# Cameras.net
KiCad netlist of a schematic drawn in Altium Designer
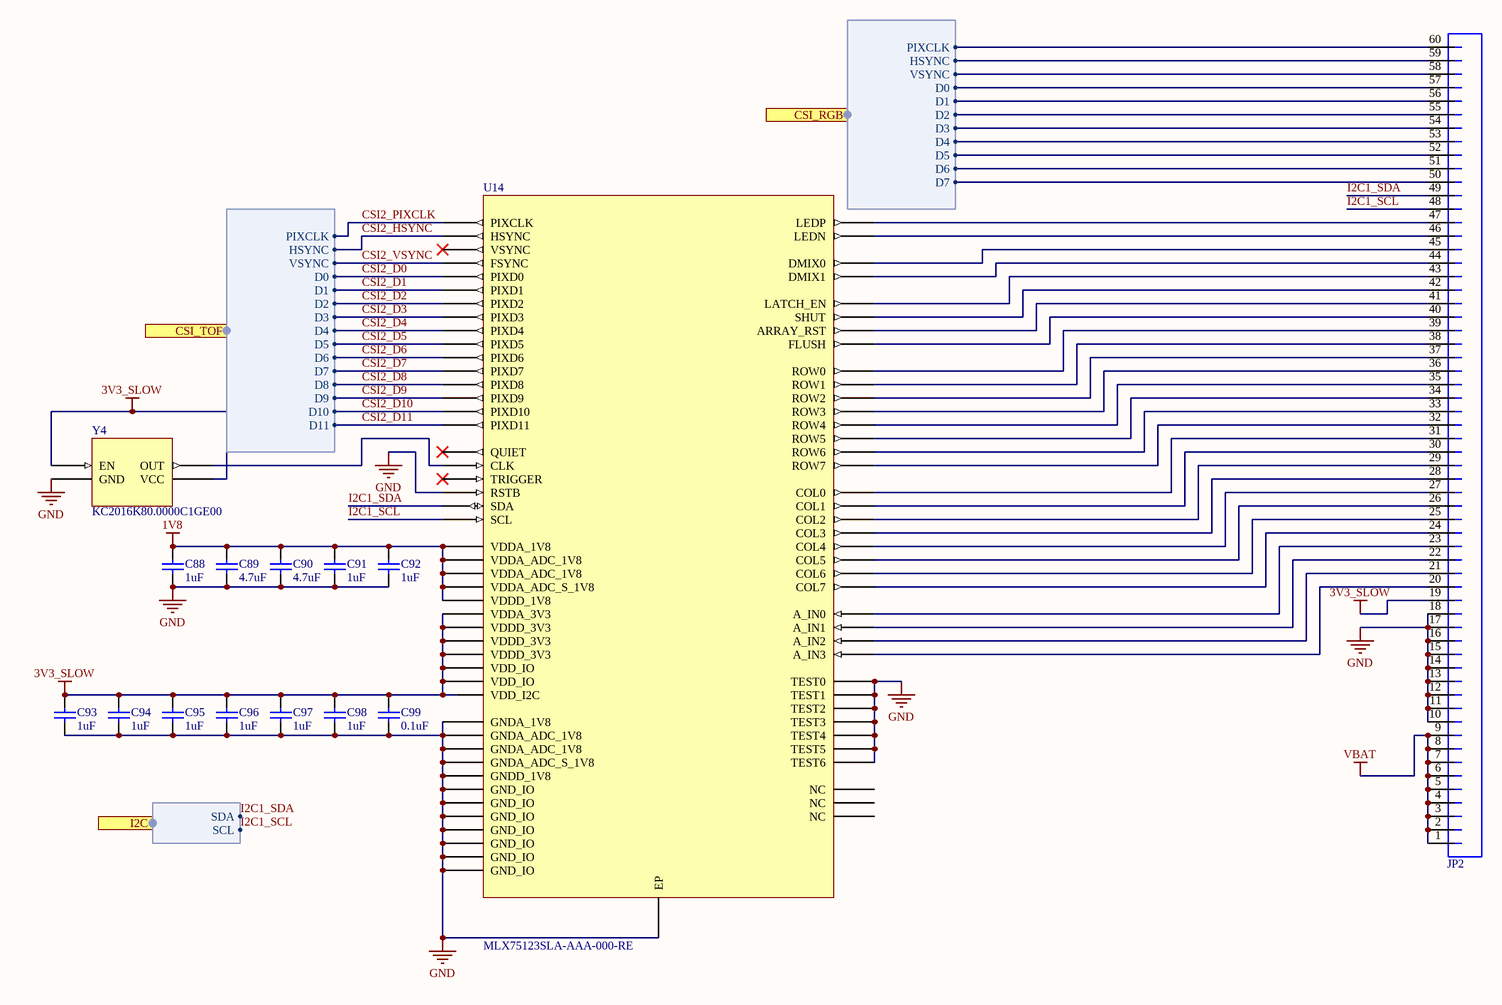
[diagram p0: Cameras.SchDoc]

(export (version "E")
  (design (tool "Eeschema 10.0.6"))
  (components
    (comp (ref "C88")
      (value "1uF")
      (footprint "C0402[1005X55]")
      (description "1uF 6.3V 10% 0402 (1005 Metric)")
      (fields (field (name "PARTNUMBER") "GRM155R70J105KA12D") (field (name "MANUFACTURER") "Murata"))
      (libsource (lib "Capacitors") (part "CAP_1uF_6.3V_0402_10%"))
    )
    (comp (ref "C89")
      (value "4.7uF")
      (footprint "C0402[1005X55]")
      (description "4.7uF 6.3V 20% 0402 (1005 Metric)")
      (fields (field (name "PARTNUMBER") "GRM155R60J475ME47D") (field (name "MANUFACTURER") "Murata"))
      (libsource (lib "Capacitors") (part "CAP_4.7uF_6.3V_0402_20%"))
    )
    (comp (ref "C90")
      (value "4.7uF")
      (footprint "C0402[1005X55]")
      (description "4.7uF 6.3V 20% 0402 (1005 Metric)")
      (fields (field (name "PARTNUMBER") "GRM155R60J475ME47D") (field (name "MANUFACTURER") "Murata"))
      (libsource (lib "Capacitors") (part "CAP_4.7uF_6.3V_0402_20%"))
    )
    (comp (ref "C91")
      (value "1uF")
      (footprint "C0402[1005X55]")
      (description "1uF 6.3V 10% 0402 (1005 Metric)")
      (fields (field (name "PARTNUMBER") "GRM155R70J105KA12D") (field (name "MANUFACTURER") "Murata"))
      (libsource (lib "Capacitors") (part "CAP_1uF_6.3V_0402_10%"))
    )
    (comp (ref "C92")
      (value "1uF")
      (footprint "C0402[1005X55]")
      (description "1uF 6.3V 10% 0402 (1005 Metric)")
      (fields (field (name "PARTNUMBER") "GRM155R70J105KA12D") (field (name "MANUFACTURER") "Murata"))
      (libsource (lib "Capacitors") (part "CAP_1uF_6.3V_0402_10%"))
    )
    (comp (ref "C93")
      (value "1uF")
      (footprint "C0402[1005X55]")
      (description "1uF 6.3V 10% 0402 (1005 Metric)")
      (fields (field (name "PARTNUMBER") "GRM155R70J105KA12D") (field (name "MANUFACTURER") "Murata"))
      (libsource (lib "Capacitors") (part "CAP_1uF_6.3V_0402_10%"))
    )
    (comp (ref "C94")
      (value "1uF")
      (footprint "C0402[1005X55]")
      (description "1uF 6.3V 10% 0402 (1005 Metric)")
      (fields (field (name "PARTNUMBER") "GRM155R70J105KA12D") (field (name "MANUFACTURER") "Murata"))
      (libsource (lib "Capacitors") (part "CAP_1uF_6.3V_0402_10%"))
    )
    (comp (ref "C95")
      (value "1uF")
      (footprint "C0402[1005X55]")
      (description "1uF 6.3V 10% 0402 (1005 Metric)")
      (fields (field (name "PARTNUMBER") "GRM155R70J105KA12D") (field (name "MANUFACTURER") "Murata"))
      (libsource (lib "Capacitors") (part "CAP_1uF_6.3V_0402_10%"))
    )
    (comp (ref "C96")
      (value "1uF")
      (footprint "C0402[1005X55]")
      (description "1uF 6.3V 10% 0402 (1005 Metric)")
      (fields (field (name "PARTNUMBER") "GRM155R70J105KA12D") (field (name "MANUFACTURER") "Murata"))
      (libsource (lib "Capacitors") (part "CAP_1uF_6.3V_0402_10%"))
    )
    (comp (ref "C97")
      (value "1uF")
      (footprint "C0402[1005X55]")
      (description "1uF 6.3V 10% 0402 (1005 Metric)")
      (fields (field (name "PARTNUMBER") "GRM155R70J105KA12D") (field (name "MANUFACTURER") "Murata"))
      (libsource (lib "Capacitors") (part "CAP_1uF_6.3V_0402_10%"))
    )
    (comp (ref "C98")
      (value "1uF")
      (footprint "C0402[1005X55]")
      (description "1uF 6.3V 10% 0402 (1005 Metric)")
      (fields (field (name "PARTNUMBER") "GRM155R70J105KA12D") (field (name "MANUFACTURER") "Murata"))
      (libsource (lib "Capacitors") (part "CAP_1uF_6.3V_0402_10%"))
    )
    (comp (ref "C99")
      (value "0.1uF")
      (footprint "C0402[1005X55]")
      (description "0.1uF 6.3V 10% 0402 (1005 Metric)")
      (fields (field (name "PARTNUMBER") "GRM155R70J104KA01D") (field (name "MANUFACTURER") "Murata"))
      (libsource (lib "Capacitors") (part "CAP_0.1uF_6.3V_0402_10%"))
    )
    (comp (ref "JP2")
      (value "JST_JMD_60_HORZ")
      (footprint "JST-JMD-60-SMD-HORZ")
      (fields
        (field (name "MANUFACTURER") "JST Sales America, Inc.")
        (field (name "PARTNUMBER") "60PS-JMDSS-G-1-TF")
      )
      (libsource (lib "Connectors") (part "JST_JMD_60_HORZ"))
    )
    (comp (ref "U14")
      (value "MLX75123SLA-AAA-000-RE")
      (footprint "AQFN-84")
      (description "Sensor Interface ToF Companion Chip")
      (fields (field (name "MANUFACTURER") "Melexis"))
      (libsource (lib "ICs") (part "MLX75123SLA-AAA-000-RE"))
    )
    (comp (ref "Y4")
      (value "KC2016K80.0000C1GE00")
      (footprint "KC2016K")
      (description "OSC XO 80.0000MHZ CMOS SMD")
      (fields (field (name "MANUFACTURER") "AVX"))
      (libsource (lib "Components") (part "KC2016K80.0000C1GE00"))
    )
  )
  (nets
    (net (code "4") (name "/CSI2_D0") (class "Default")
      (node (ref "U14") (pin "A30") (pinfunction "PIXD0_A30") (pintype "output"))
    )
    (net (code "5") (name "/CSI2_D1") (class "Default")
      (node (ref "U14") (pin "B27") (pinfunction "PIXD1_B27") (pintype "output"))
    )
    (net (code "6") (name "/CSI2_D2") (class "Default")
      (node (ref "U14") (pin "A29") (pinfunction "PIXD2_A29") (pintype "output"))
    )
    (net (code "7") (name "/CSI2_D3") (class "Default")
      (node (ref "U14") (pin "B26") (pinfunction "PIXD3_B26") (pintype "output"))
    )
    (net (code "8") (name "/CSI2_D4") (class "Default")
      (node (ref "U14") (pin "A28") (pinfunction "PIXD4_A28") (pintype "output"))
    )
    (net (code "9") (name "/CSI2_D5") (class "Default")
      (node (ref "U14") (pin "B25") (pinfunction "PIXD5_B25") (pintype "output"))
    )
    (net (code "10") (name "/CSI2_D6") (class "Default")
      (node (ref "U14") (pin "A27") (pinfunction "PIXD6_A27") (pintype "output"))
    )
    (net (code "11") (name "/CSI2_D7") (class "Default")
      (node (ref "U14") (pin "B24") (pinfunction "PIXD7_B24") (pintype "output"))
    )
    (net (code "12") (name "/CSI2_D8") (class "Default")
      (node (ref "U14") (pin "A26") (pinfunction "PIXD8_A26") (pintype "output"))
    )
    (net (code "13") (name "/CSI2_D9") (class "Default")
      (node (ref "U14") (pin "B23") (pinfunction "PIXD9_B23") (pintype "output"))
    )
    (net (code "14") (name "/CSI2_D10") (class "Default")
      (node (ref "U14") (pin "A25") (pinfunction "PIXD10_A25") (pintype "output"))
    )
    (net (code "15") (name "/CSI2_D11") (class "Default")
      (node (ref "U14") (pin "B22") (pinfunction "PIXD11_B22") (pintype "output"))
    )
    (net (code "16") (name "/CSI2_HSYNC") (class "Default")
      (node (ref "U14") (pin "B29") (pinfunction "HSYNC_B29") (pintype "output"))
    )
    (net (code "17") (name "/CSI2_PIXCLK") (class "Default")
      (node (ref "U14") (pin "B28") (pinfunction "PIXCLK_B28") (pintype "output"))
    )
    (net (code "18") (name "/CSI2_VSYNC") (class "Default")
      (node (ref "U14") (pin "A31") (pinfunction "FSYNC_A31") (pintype "output"))
    )
    (net (code "19") (name "/I2C1_SCL") (class "Default")
      (node (ref "JP2") (pin "48") (pinfunction "48_48") (pintype "passive"))
      (node (ref "U14") (pin "A12") (pinfunction "SCL_A12") (pintype "input"))
    )
    (net (code "20") (name "/I2C1_SDA") (class "Default")
      (node (ref "JP2") (pin "49") (pinfunction "49_49") (pintype "passive"))
      (node (ref "U14") (pin "B11") (pinfunction "SDA_B11") (pintype "bidirectional"))
    )
    (net (code "24") (name "1V8") (class "Default")
      (node (ref "C88") (pin "2") (pinfunction "2_2") (pintype "passive"))
      (node (ref "C89") (pin "2") (pinfunction "2_2") (pintype "passive"))
      (node (ref "C90") (pin "2") (pinfunction "2_2") (pintype "passive"))
      (node (ref "C91") (pin "2") (pinfunction "2_2") (pintype "passive"))
      (node (ref "C92") (pin "2") (pinfunction "2_2") (pintype "passive"))
      (node (ref "U14") (pin "A10") (pinfunction "VDDA_ADC_S_1V8_A10") (pintype "power_in"))
      (node (ref "U14") (pin "A9") (pinfunction "VDDA_ADC_1V8_A9") (pintype "power_in"))
      (node (ref "U14") (pin "B14") (pinfunction "VDDA_1V8_B14") (pintype "power_in"))
      (node (ref "U14") (pin "B20") (pinfunction "VDDD_1V8_B20") (pintype "power_in"))
      (node (ref "U14") (pin "B5") (pinfunction "VDDA_ADC_1V8_B5") (pintype "power_in"))
    )
    (net (code "25") (name "3V3_SLOW") (class "Default")
      (node (ref "C93") (pin "2") (pinfunction "2_2") (pintype "passive"))
      (node (ref "C94") (pin "2") (pinfunction "2_2") (pintype "passive"))
      (node (ref "C95") (pin "2") (pinfunction "2_2") (pintype "passive"))
      (node (ref "C96") (pin "2") (pinfunction "2_2") (pintype "passive"))
      (node (ref "C97") (pin "2") (pinfunction "2_2") (pintype "passive"))
      (node (ref "C98") (pin "2") (pinfunction "2_2") (pintype "passive"))
      (node (ref "C99") (pin "2") (pinfunction "2_2") (pintype "passive"))
      (node (ref "JP2") (pin "19") (pinfunction "19_19") (pintype "passive"))
      (node (ref "U14") (pin "A36") (pinfunction "VDDD_3V3_A36") (pintype "power_in"))
      (node (ref "U14") (pin "B12") (pinfunction "VDD_I2C_B12") (pintype "power_in"))
      (node (ref "U14") (pin "B17") (pinfunction "VDDD_3V3_B17") (pintype "power_in"))
      (node (ref "U14") (pin "B21") (pinfunction "VDD_IO_B21") (pintype "power_in"))
      (node (ref "U14") (pin "B30") (pinfunction "VDD_IO_B30") (pintype "power_in"))
      (node (ref "U14") (pin "B38") (pinfunction "VDDD_3V3_B38") (pintype "power_in"))
      (node (ref "U14") (pin "B4") (pinfunction "VDDA_3V3_B4") (pintype "power_in"))
      (node (ref "Y4") (pin "1") (pinfunction "EN_1") (pintype "input"))
      (node (ref "Y4") (pin "4") (pinfunction "VCC_4") (pintype "power_in"))
    )
    (net (code "26") (name "GND") (class "Default")
      (node (ref "C88") (pin "1") (pinfunction "1_1") (pintype "passive"))
      (node (ref "C89") (pin "1") (pinfunction "1_1") (pintype "passive"))
      (node (ref "C90") (pin "1") (pinfunction "1_1") (pintype "passive"))
      (node (ref "C91") (pin "1") (pinfunction "1_1") (pintype "passive"))
      (node (ref "C92") (pin "1") (pinfunction "1_1") (pintype "passive"))
      (node (ref "C93") (pin "1") (pinfunction "1_1") (pintype "passive"))
      (node (ref "C94") (pin "1") (pinfunction "1_1") (pintype "passive"))
      (node (ref "C95") (pin "1") (pinfunction "1_1") (pintype "passive"))
      (node (ref "C96") (pin "1") (pinfunction "1_1") (pintype "passive"))
      (node (ref "C97") (pin "1") (pinfunction "1_1") (pintype "passive"))
      (node (ref "C98") (pin "1") (pinfunction "1_1") (pintype "passive"))
      (node (ref "C99") (pin "1") (pinfunction "1_1") (pintype "passive"))
      (node (ref "JP2") (pin "10") (pinfunction "10_10") (pintype "passive"))
      (node (ref "JP2") (pin "11") (pinfunction "11_11") (pintype "passive"))
      (node (ref "JP2") (pin "12") (pinfunction "12_12") (pintype "passive"))
      (node (ref "JP2") (pin "13") (pinfunction "13_13") (pintype "passive"))
      (node (ref "JP2") (pin "14") (pinfunction "14_14") (pintype "passive"))
      (node (ref "JP2") (pin "15") (pinfunction "15_15") (pintype "passive"))
      (node (ref "JP2") (pin "16") (pinfunction "16_16") (pintype "passive"))
      (node (ref "JP2") (pin "17") (pinfunction "17_17") (pintype "passive"))
      (node (ref "JP2") (pin "18") (pinfunction "18_18") (pintype "passive"))
      (node (ref "U14") (pin "A11") (pinfunction "TEST5_A11") (pintype "passive"))
      (node (ref "U14") (pin "A14") (pinfunction "RSTB_A14") (pintype "input"))
      (node (ref "U14") (pin "A16") (pinfunction "GNDA_1V8_A16") (pintype "power_in"))
      (node (ref "U14") (pin "A17") (pinfunction "TEST3_A17") (pintype "passive"))
      (node (ref "U14") (pin "A18") (pinfunction "GND_IO_A18") (pintype "power_in"))
      (node (ref "U14") (pin "A21") (pinfunction "TEST0_A21") (pintype "passive"))
      (node (ref "U14") (pin "A22") (pinfunction "GNDD_1V8_A22") (pintype "power_in"))
      (node (ref "U14") (pin "A24") (pinfunction "GND_IO_A24") (pintype "power_in"))
      (node (ref "U14") (pin "A33") (pinfunction "GND_IO_A33") (pintype "power_in"))
      (node (ref "U14") (pin "A41") (pinfunction "GND_IO_A41") (pintype "power_in"))
      (node (ref "U14") (pin "A5") (pinfunction "GNDA_ADC_1V8_A5") (pintype "power_in"))
      (node (ref "U14") (pin "A8") (pinfunction "GND_IO_A8") (pintype "power_in"))
      (node (ref "U14") (pin "B10") (pinfunction "TEST6_B10") (pintype "passive"))
      (node (ref "U14") (pin "B15") (pinfunction "GND_IO_B15") (pintype "power_in"))
      (node (ref "U14") (pin "B16") (pinfunction "TEST4_B16") (pintype "passive"))
      (node (ref "U14") (pin "B18") (pinfunction "TEST2_B18") (pintype "passive"))
      (node (ref "U14") (pin "B19") (pinfunction "TEST1_B19") (pintype "passive"))
      (node (ref "U14") (pin "B33") (pinfunction "GND_IO_B33") (pintype "power_in"))
      (node (ref "U14") (pin "B8") (pinfunction "GNDA_ADC_1V8_B8") (pintype "power_in"))
      (node (ref "U14") (pin "B9") (pinfunction "GNDA_ADC_S_1V8_B9") (pintype "power_in"))
      (node (ref "U14") (pin "EP") (pinfunction "EP_EP") (pintype "passive"))
      (node (ref "Y4") (pin "2") (pinfunction "GND_2") (pintype "power_in"))
    )
    (net (code "27") (name "Net-(U14-ARRAY_RST)") (class "Default")
      (node (ref "JP2") (pin "41") (pinfunction "41_41") (pintype "passive"))
      (node (ref "U14") (pin "A3") (pinfunction "ARRAY_RST_A3") (pintype "output"))
    )
    (net (code "28") (name "Net-(U14-A_IN0)") (class "Default")
      (node (ref "JP2") (pin "23") (pinfunction "23_23") (pintype "passive"))
      (node (ref "U14") (pin "B6") (pinfunction "A_IN0_B6") (pintype "input"))
    )
    (net (code "29") (name "Net-(U14-A_IN1)") (class "Default")
      (node (ref "JP2") (pin "22") (pinfunction "22_22") (pintype "passive"))
      (node (ref "U14") (pin "A6") (pinfunction "A_IN1_A6") (pintype "input"))
    )
    (net (code "30") (name "Net-(U14-A_IN2)") (class "Default")
      (node (ref "JP2") (pin "21") (pinfunction "21_21") (pintype "passive"))
      (node (ref "U14") (pin "A7") (pinfunction "A_IN2_A7") (pintype "input"))
    )
    (net (code "31") (name "Net-(U14-A_IN3)") (class "Default")
      (node (ref "JP2") (pin "20") (pinfunction "20_20") (pintype "passive"))
      (node (ref "U14") (pin "B7") (pinfunction "A_IN3_B7") (pintype "input"))
    )
    (net (code "32") (name "Net-(U14-CLK)") (class "Default")
      (node (ref "U14") (pin "B13") (pinfunction "CLK_B13") (pintype "input"))
      (node (ref "Y4") (pin "3") (pinfunction "OUT_3") (pintype "output"))
    )
    (net (code "33") (name "Net-(U14-COL0)") (class "Default")
      (node (ref "JP2") (pin "31") (pinfunction "31_31") (pintype "passive"))
      (node (ref "U14") (pin "B37") (pinfunction "COL0_B37") (pintype "output"))
    )
    (net (code "34") (name "Net-(U14-COL1)") (class "Default")
      (node (ref "JP2") (pin "30") (pinfunction "30_30") (pintype "passive"))
      (node (ref "U14") (pin "A40") (pinfunction "COL1_A40") (pintype "output"))
    )
    (net (code "35") (name "Net-(U14-COL2)") (class "Default")
      (node (ref "JP2") (pin "29") (pinfunction "29_29") (pintype "passive"))
      (node (ref "U14") (pin "B36") (pinfunction "COL2_B36") (pintype "output"))
    )
    (net (code "36") (name "Net-(U14-COL3)") (class "Default")
      (node (ref "JP2") (pin "28") (pinfunction "28_28") (pintype "passive"))
      (node (ref "U14") (pin "A39") (pinfunction "COL3_A39") (pintype "output"))
    )
    (net (code "37") (name "Net-(U14-COL4)") (class "Default")
      (node (ref "JP2") (pin "27") (pinfunction "27_27") (pintype "passive"))
      (node (ref "U14") (pin "B35") (pinfunction "COL4_B35") (pintype "output"))
    )
    (net (code "38") (name "Net-(U14-COL5)") (class "Default")
      (node (ref "JP2") (pin "26") (pinfunction "26_26") (pintype "passive"))
      (node (ref "U14") (pin "A38") (pinfunction "COL5_A38") (pintype "output"))
    )
    (net (code "39") (name "Net-(U14-COL6)") (class "Default")
      (node (ref "JP2") (pin "25") (pinfunction "25_25") (pintype "passive"))
      (node (ref "U14") (pin "B34") (pinfunction "COL6_B34") (pintype "output"))
    )
    (net (code "40") (name "Net-(U14-COL7)") (class "Default")
      (node (ref "JP2") (pin "24") (pinfunction "24_24") (pintype "passive"))
      (node (ref "U14") (pin "A37") (pinfunction "COL7_A37") (pintype "output"))
    )
    (net (code "41") (name "Net-(U14-DMIX0)") (class "Default")
      (node (ref "JP2") (pin "45") (pinfunction "45_45") (pintype "passive"))
      (node (ref "U14") (pin "A35") (pinfunction "DMIX0_A35") (pintype "output"))
    )
    (net (code "42") (name "Net-(U14-DMIX1)") (class "Default")
      (node (ref "JP2") (pin "44") (pinfunction "44_44") (pintype "passive"))
      (node (ref "U14") (pin "B32") (pinfunction "DMIX1_B32") (pintype "output"))
    )
    (net (code "43") (name "Net-(U14-FLUSH)") (class "Default")
      (node (ref "JP2") (pin "40") (pinfunction "40_40") (pintype "passive"))
      (node (ref "U14") (pin "B3") (pinfunction "FLUSH_B3") (pintype "output"))
    )
    (net (code "44") (name "Net-(U14-LATCH_EN)") (class "Default")
      (node (ref "JP2") (pin "43") (pinfunction "43_43") (pintype "passive"))
      (node (ref "U14") (pin "A4") (pinfunction "LATCH_EN_A4") (pintype "output"))
    )
    (net (code "45") (name "Net-(U14-LEDN)") (class "Default")
      (node (ref "JP2") (pin "46") (pinfunction "46_46") (pintype "passive"))
      (node (ref "U14") (pin "A34") (pinfunction "LEDN_A34") (pintype "output"))
    )
    (net (code "46") (name "Net-(U14-LEDP)") (class "Default")
      (node (ref "JP2") (pin "47") (pinfunction "47_47") (pintype "passive"))
      (node (ref "U14") (pin "B31") (pinfunction "LEDP_B31") (pintype "output"))
    )
    (net (code "47") (name "Net-(U14-ROW0)") (class "Default")
      (node (ref "JP2") (pin "39") (pinfunction "39_39") (pintype "passive"))
      (node (ref "U14") (pin "A42") (pinfunction "ROW0_A42") (pintype "output"))
    )
    (net (code "48") (name "Net-(U14-ROW1)") (class "Default")
      (node (ref "JP2") (pin "38") (pinfunction "38_38") (pintype "passive"))
      (node (ref "U14") (pin "B39") (pinfunction "ROW1_B39") (pintype "output"))
    )
    (net (code "49") (name "Net-(U14-ROW2)") (class "Default")
      (node (ref "JP2") (pin "37") (pinfunction "37_37") (pintype "passive"))
      (node (ref "U14") (pin "A43") (pinfunction "ROW2_A43") (pintype "output"))
    )
    (net (code "50") (name "Net-(U14-ROW3)") (class "Default")
      (node (ref "JP2") (pin "36") (pinfunction "36_36") (pintype "passive"))
      (node (ref "U14") (pin "B40") (pinfunction "ROW3_B40") (pintype "output"))
    )
    (net (code "51") (name "Net-(U14-ROW4)") (class "Default")
      (node (ref "JP2") (pin "35") (pinfunction "35_35") (pintype "passive"))
      (node (ref "U14") (pin "A44") (pinfunction "ROW4_A44") (pintype "output"))
    )
    (net (code "52") (name "Net-(U14-ROW5)") (class "Default")
      (node (ref "JP2") (pin "34") (pinfunction "34_34") (pintype "passive"))
      (node (ref "U14") (pin "A1") (pinfunction "ROW5_A1") (pintype "output"))
    )
    (net (code "53") (name "Net-(U14-ROW6)") (class "Default")
      (node (ref "JP2") (pin "33") (pinfunction "33_33") (pintype "passive"))
      (node (ref "U14") (pin "B1") (pinfunction "ROW6_B1") (pintype "output"))
    )
    (net (code "54") (name "Net-(U14-ROW7)") (class "Default")
      (node (ref "JP2") (pin "32") (pinfunction "32_32") (pintype "passive"))
      (node (ref "U14") (pin "A2") (pinfunction "ROW7_A2") (pintype "output"))
    )
    (net (code "55") (name "Net-(U14-SHUT)") (class "Default")
      (node (ref "JP2") (pin "42") (pinfunction "42_42") (pintype "passive"))
      (node (ref "U14") (pin "B2") (pinfunction "SHUT_B2") (pintype "output"))
    )
    (net (code "56") (name "VBAT") (class "Default")
      (node (ref "JP2") (pin "1") (pinfunction "1_1") (pintype "passive"))
      (node (ref "JP2") (pin "2") (pinfunction "2_2") (pintype "passive"))
      (node (ref "JP2") (pin "3") (pinfunction "3_3") (pintype "passive"))
      (node (ref "JP2") (pin "4") (pinfunction "4_4") (pintype "passive"))
      (node (ref "JP2") (pin "5") (pinfunction "5_5") (pintype "passive"))
      (node (ref "JP2") (pin "6") (pinfunction "6_6") (pintype "passive"))
      (node (ref "JP2") (pin "7") (pinfunction "7_7") (pintype "passive"))
      (node (ref "JP2") (pin "8") (pinfunction "8_8") (pintype "passive"))
      (node (ref "JP2") (pin "9") (pinfunction "9_9") (pintype "passive"))
    )
    (net (code "57") (name "unconnected-(JP2-Pad50)") (class "Default")
      (node (ref "JP2") (pin "50") (pinfunction "50_50") (pintype "passive"))
    )
    (net (code "58") (name "unconnected-(JP2-Pad51)") (class "Default")
      (node (ref "JP2") (pin "51") (pinfunction "51_51") (pintype "passive"))
    )
    (net (code "59") (name "unconnected-(JP2-Pad52)") (class "Default")
      (node (ref "JP2") (pin "52") (pinfunction "52_52") (pintype "passive"))
    )
    (net (code "60") (name "unconnected-(JP2-Pad53)") (class "Default")
      (node (ref "JP2") (pin "53") (pinfunction "53_53") (pintype "passive"))
    )
    (net (code "61") (name "unconnected-(JP2-Pad54)") (class "Default")
      (node (ref "JP2") (pin "54") (pinfunction "54_54") (pintype "passive"))
    )
    (net (code "62") (name "unconnected-(JP2-Pad55)") (class "Default")
      (node (ref "JP2") (pin "55") (pinfunction "55_55") (pintype "passive"))
    )
    (net (code "63") (name "unconnected-(JP2-Pad56)") (class "Default")
      (node (ref "JP2") (pin "56") (pinfunction "56_56") (pintype "passive"))
    )
    (net (code "64") (name "unconnected-(JP2-Pad57)") (class "Default")
      (node (ref "JP2") (pin "57") (pinfunction "57_57") (pintype "passive"))
    )
    (net (code "65") (name "unconnected-(JP2-Pad58)") (class "Default")
      (node (ref "JP2") (pin "58") (pinfunction "58_58") (pintype "passive"))
    )
    (net (code "66") (name "unconnected-(JP2-Pad59)") (class "Default")
      (node (ref "JP2") (pin "59") (pinfunction "59_59") (pintype "passive"))
    )
    (net (code "67") (name "unconnected-(JP2-Pad60)") (class "Default")
      (node (ref "JP2") (pin "60") (pinfunction "60_60") (pintype "passive"))
    )
    (net (code "68") (name "unconnected-(U14-NC-PadA19)") (class "Default")
      (node (ref "U14") (pin "A19") (pinfunction "NC_A19") (pintype "passive"))
    )
    (net (code "69") (name "unconnected-(U14-NC-PadA20)") (class "Default")
      (node (ref "U14") (pin "A20") (pinfunction "NC_A20") (pintype "passive"))
    )
    (net (code "70") (name "unconnected-(U14-NC-PadA23)") (class "Default")
      (node (ref "U14") (pin "A23") (pinfunction "NC_A23") (pintype "passive"))
    )
    (net (code "71") (name "unconnected-(U14-QUIET-PadA15)") (class "Default")
      (node (ref "U14") (pin "A15") (pinfunction "QUIET_A15") (pintype "output+no_connect"))
    )
    (net (code "72") (name "unconnected-(U14-TRIGGER-PadA13)") (class "Default")
      (node (ref "U14") (pin "A13") (pinfunction "TRIGGER_A13") (pintype "input+no_connect"))
    )
    (net (code "73") (name "unconnected-(U14-VSYNC-PadA32)") (class "Default")
      (node (ref "U14") (pin "A32") (pinfunction "VSYNC_A32") (pintype "output+no_connect"))
    )
  )
)
